# JMP_1_1.net
KiCad netlist of a schematic drawn in EAGLE
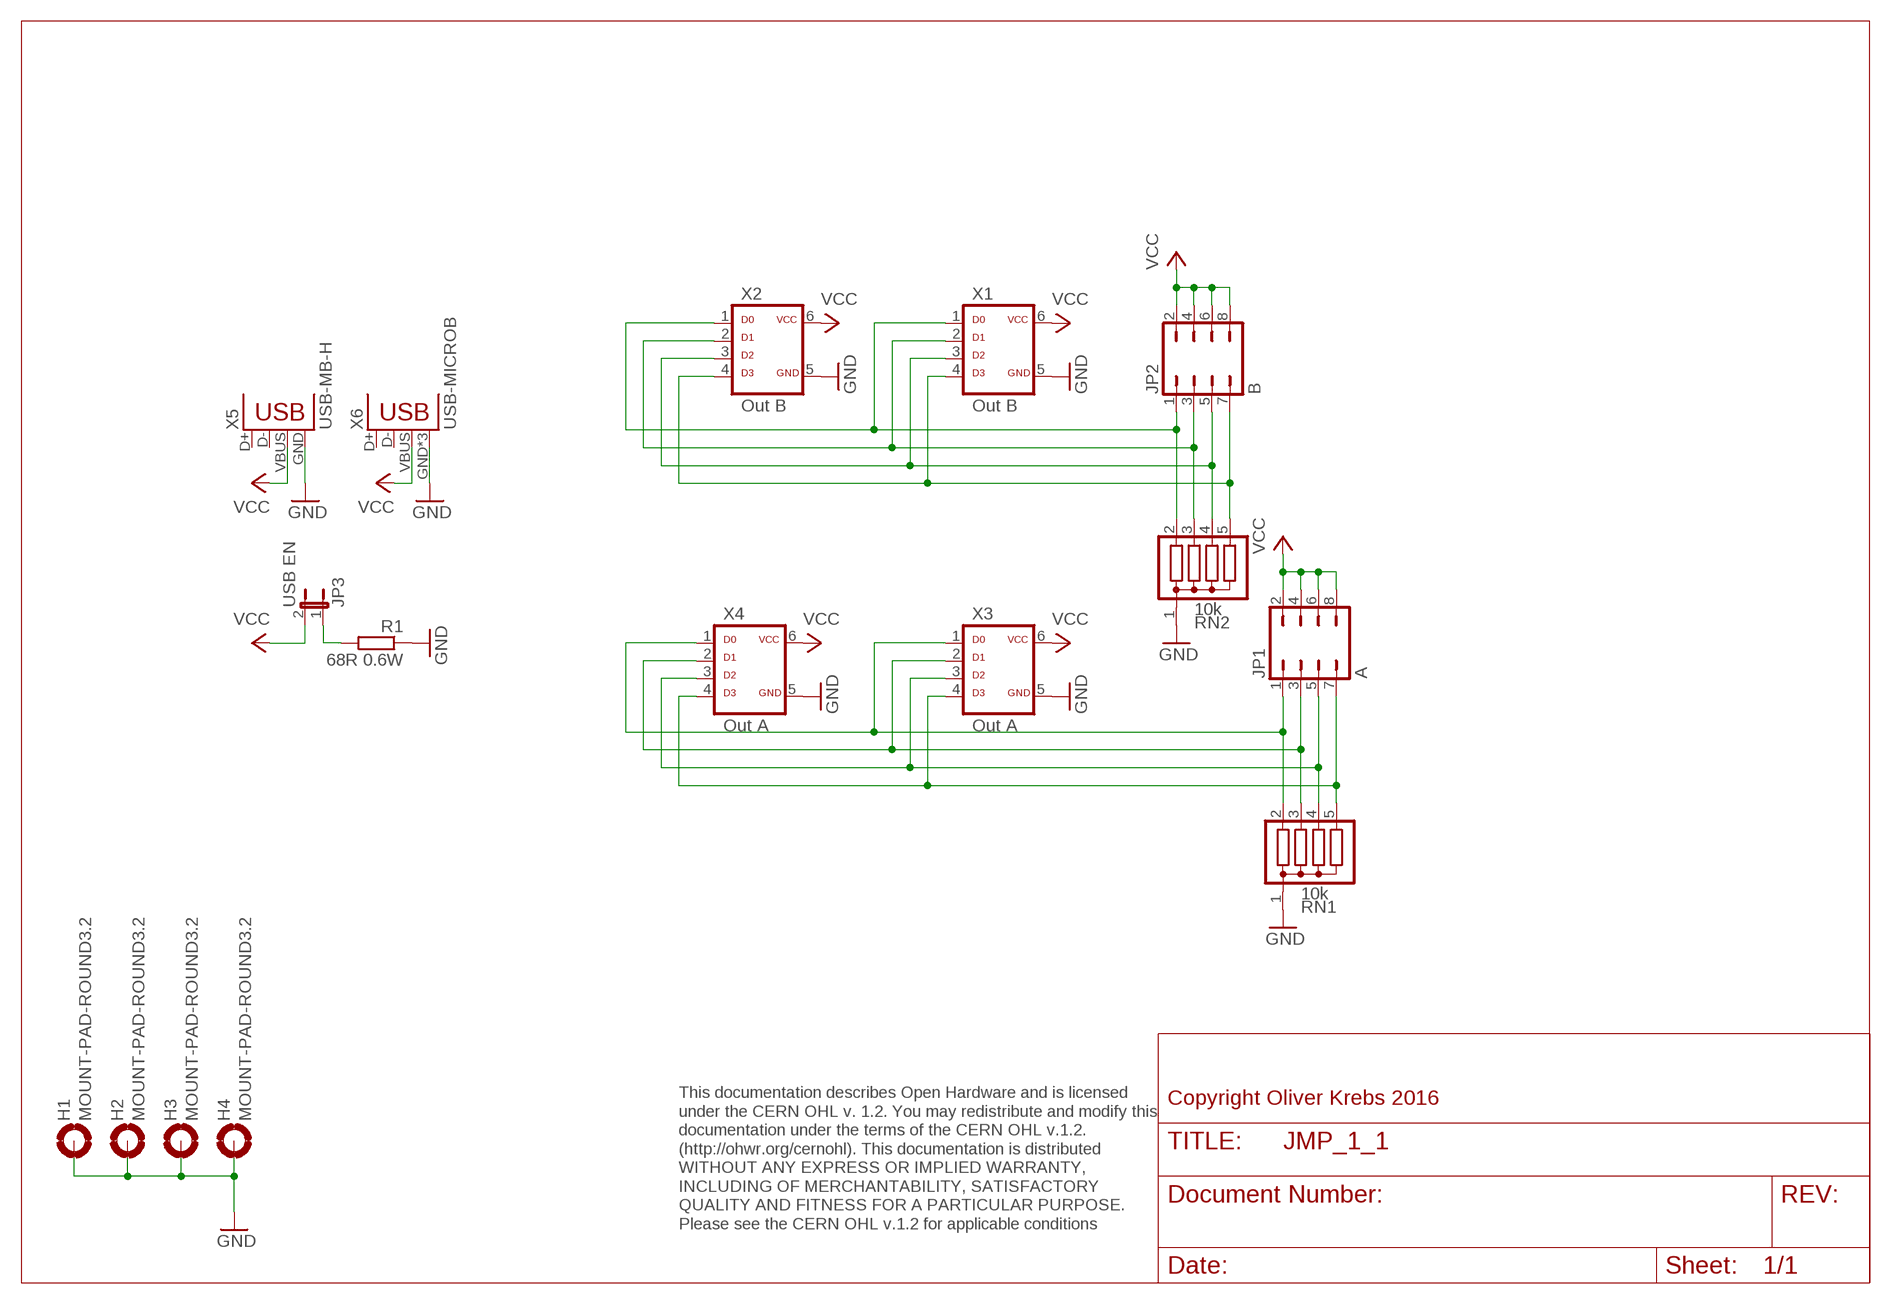
[diagram p0: schematic, sheet 1]

(export (version "E")
  (design (tool "Eeschema 10.0.6"))
  (components
    (comp (ref "H1")
      (value "MOUNT-PAD-ROUND3.2")
      (footprint "eagle-import:3,2-PAD")
      (libsource (lib "eagle-import") (part "MOUNT-PAD-ROUND3.2"))
    )
    (comp (ref "H2")
      (value "MOUNT-PAD-ROUND3.2")
      (footprint "eagle-import:3,2-PAD")
      (libsource (lib "eagle-import") (part "MOUNT-PAD-ROUND3.2"))
    )
    (comp (ref "H3")
      (value "MOUNT-PAD-ROUND3.2")
      (footprint "eagle-import:3,2-PAD")
      (libsource (lib "eagle-import") (part "MOUNT-PAD-ROUND3.2"))
    )
    (comp (ref "H4")
      (value "MOUNT-PAD-ROUND3.2")
      (footprint "eagle-import:3,2-PAD")
      (libsource (lib "eagle-import") (part "MOUNT-PAD-ROUND3.2"))
    )
    (comp (ref "JP1")
      (value "A")
      (footprint "eagle-import:JP4Q")
      (libsource (lib "eagle-import") (part "JP4Q"))
    )
    (comp (ref "JP2")
      (value "B")
      (footprint "eagle-import:JP4Q")
      (libsource (lib "eagle-import") (part "JP4Q"))
    )
    (comp (ref "JP3")
      (value "USB EN")
      (footprint "eagle-import:JP1")
      (libsource (lib "eagle-import") (part "JP1E"))
    )
    (comp (ref "R1")
      (value "68R 0.6W")
      (footprint "eagle-import:0207_10")
      (libsource (lib "eagle-import") (part "R-EU_0207/10"))
    )
    (comp (ref "RN1")
      (value "10k")
      (footprint "eagle-import:SIL5")
      (libsource (lib "eagle-import") (part "G04R"))
    )
    (comp (ref "RN2")
      (value "10k")
      (footprint "eagle-import:SIL5")
      (libsource (lib "eagle-import") (part "G04R"))
    )
    (comp (ref "X1")
      (value "Out B")
      (footprint "eagle-import:ML-6")
      (libsource (lib "eagle-import") (part "ML6D"))
    )
    (comp (ref "X2")
      (value "Out B")
      (footprint "eagle-import:ML-6")
      (libsource (lib "eagle-import") (part "ML6D"))
    )
    (comp (ref "X3")
      (value "Out A")
      (footprint "eagle-import:ML-6")
      (libsource (lib "eagle-import") (part "ML6D"))
    )
    (comp (ref "X4")
      (value "Out A")
      (footprint "eagle-import:ML-6")
      (libsource (lib "eagle-import") (part "ML6D"))
    )
    (comp (ref "X5")
      (value "USB-MB-H")
      (footprint "eagle-import:USB-MB-H")
      (libsource (lib "eagle-import") (part "USB-MB-H"))
    )
    (comp (ref "X6")
      (value "USB-MICROB")
      (footprint "eagle-import:USB-MICROB")
      (libsource (lib "eagle-import") (part "USB-MICROB"))
    )
  )
  (nets
    (net (code "1") (name "GND") (class "Default")
      (node (ref "H1") (pin "B3,2") (pinfunction "MOUNT_B3,2") (pintype "passive"))
      (node (ref "H2") (pin "B3,2") (pinfunction "MOUNT_B3,2") (pintype "passive"))
      (node (ref "H3") (pin "B3,2") (pinfunction "MOUNT_B3,2") (pintype "passive"))
      (node (ref "H4") (pin "B3,2") (pinfunction "MOUNT_B3,2") (pintype "passive"))
      (node (ref "R1") (pin "1") (pinfunction "1_1") (pintype "passive"))
      (node (ref "RN1") (pin "1") (pinfunction "1_1") (pintype "passive"))
      (node (ref "RN2") (pin "1") (pinfunction "1_1") (pintype "passive"))
      (node (ref "X1") (pin "5") (pinfunction "5_5") (pintype "passive"))
      (node (ref "X2") (pin "5") (pinfunction "5_5") (pintype "passive"))
      (node (ref "X3") (pin "5") (pinfunction "5_5") (pintype "passive"))
      (node (ref "X4") (pin "5") (pinfunction "5_5") (pintype "passive"))
      (node (ref "X5") (pin "GND") (pinfunction "GND_GND") (pintype "bidirectional"))
      (node (ref "X6") (pin "GND") (pinfunction "GND_GND") (pintype "bidirectional"))
      (node (ref "X6") (pin "MT1") (pinfunction "GND_MT1") (pintype "bidirectional"))
      (node (ref "X6") (pin "MT2") (pinfunction "GND_MT2") (pintype "bidirectional"))
    )
    (net (code "2") (name "Net-(JP1-Pad1)") (class "Default")
      (node (ref "JP1") (pin "1") (pinfunction "1_1") (pintype "passive"))
      (node (ref "RN1") (pin "2") (pinfunction "2_2") (pintype "passive"))
      (node (ref "X3") (pin "1") (pinfunction "1_1") (pintype "passive"))
      (node (ref "X4") (pin "1") (pinfunction "1_1") (pintype "passive"))
    )
    (net (code "3") (name "Net-(JP1-Pad3)") (class "Default")
      (node (ref "JP1") (pin "3") (pinfunction "3_3") (pintype "passive"))
      (node (ref "RN1") (pin "3") (pinfunction "3_3") (pintype "passive"))
      (node (ref "X3") (pin "2") (pinfunction "2_2") (pintype "passive"))
      (node (ref "X4") (pin "2") (pinfunction "2_2") (pintype "passive"))
    )
    (net (code "4") (name "Net-(JP1-Pad5)") (class "Default")
      (node (ref "JP1") (pin "5") (pinfunction "5_5") (pintype "passive"))
      (node (ref "RN1") (pin "4") (pinfunction "4_4") (pintype "passive"))
      (node (ref "X3") (pin "3") (pinfunction "3_3") (pintype "passive"))
      (node (ref "X4") (pin "3") (pinfunction "3_3") (pintype "passive"))
    )
    (net (code "5") (name "Net-(JP1-Pad7)") (class "Default")
      (node (ref "JP1") (pin "7") (pinfunction "7_7") (pintype "passive"))
      (node (ref "RN1") (pin "5") (pinfunction "5_5") (pintype "passive"))
      (node (ref "X3") (pin "4") (pinfunction "4_4") (pintype "passive"))
      (node (ref "X4") (pin "4") (pinfunction "4_4") (pintype "passive"))
    )
    (net (code "6") (name "Net-(JP2-Pad1)") (class "Default")
      (node (ref "JP2") (pin "1") (pinfunction "1_1") (pintype "passive"))
      (node (ref "RN2") (pin "2") (pinfunction "2_2") (pintype "passive"))
      (node (ref "X1") (pin "1") (pinfunction "1_1") (pintype "passive"))
      (node (ref "X2") (pin "1") (pinfunction "1_1") (pintype "passive"))
    )
    (net (code "7") (name "Net-(JP2-Pad3)") (class "Default")
      (node (ref "JP2") (pin "3") (pinfunction "3_3") (pintype "passive"))
      (node (ref "RN2") (pin "3") (pinfunction "3_3") (pintype "passive"))
      (node (ref "X1") (pin "2") (pinfunction "2_2") (pintype "passive"))
      (node (ref "X2") (pin "2") (pinfunction "2_2") (pintype "passive"))
    )
    (net (code "8") (name "Net-(JP2-Pad5)") (class "Default")
      (node (ref "JP2") (pin "5") (pinfunction "5_5") (pintype "passive"))
      (node (ref "RN2") (pin "4") (pinfunction "4_4") (pintype "passive"))
      (node (ref "X1") (pin "3") (pinfunction "3_3") (pintype "passive"))
      (node (ref "X2") (pin "3") (pinfunction "3_3") (pintype "passive"))
    )
    (net (code "9") (name "Net-(JP2-Pad7)") (class "Default")
      (node (ref "JP2") (pin "7") (pinfunction "7_7") (pintype "passive"))
      (node (ref "RN2") (pin "5") (pinfunction "5_5") (pintype "passive"))
      (node (ref "X1") (pin "4") (pinfunction "4_4") (pintype "passive"))
      (node (ref "X2") (pin "4") (pinfunction "4_4") (pintype "passive"))
    )
    (net (code "10") (name "Net-(JP3-Pad1)") (class "Default")
      (node (ref "JP3") (pin "1") (pinfunction "1_1") (pintype "passive"))
      (node (ref "R1") (pin "2") (pinfunction "2_2") (pintype "passive"))
    )
    (net (code "11") (name "VCC") (class "Default")
      (node (ref "JP1") (pin "2") (pinfunction "2_2") (pintype "passive"))
      (node (ref "JP1") (pin "4") (pinfunction "4_4") (pintype "passive"))
      (node (ref "JP1") (pin "6") (pinfunction "6_6") (pintype "passive"))
      (node (ref "JP1") (pin "8") (pinfunction "8_8") (pintype "passive"))
      (node (ref "JP2") (pin "2") (pinfunction "2_2") (pintype "passive"))
      (node (ref "JP2") (pin "4") (pinfunction "4_4") (pintype "passive"))
      (node (ref "JP2") (pin "6") (pinfunction "6_6") (pintype "passive"))
      (node (ref "JP2") (pin "8") (pinfunction "8_8") (pintype "passive"))
      (node (ref "JP3") (pin "2") (pinfunction "2_2") (pintype "passive"))
      (node (ref "X1") (pin "6") (pinfunction "6_6") (pintype "passive"))
      (node (ref "X2") (pin "6") (pinfunction "6_6") (pintype "passive"))
      (node (ref "X3") (pin "6") (pinfunction "6_6") (pintype "passive"))
      (node (ref "X4") (pin "6") (pinfunction "6_6") (pintype "passive"))
      (node (ref "X5") (pin "VBUS") (pinfunction "VBUS_VBUS") (pintype "bidirectional"))
      (node (ref "X6") (pin "VBUS") (pinfunction "VBUS_VBUS") (pintype "bidirectional"))
    )
    (net (code "12") (name "unconnected-(X5-PadD+)") (class "Default")
      (node (ref "X5") (pin "D+") (pinfunction "D+_D+") (pintype "bidirectional"))
    )
    (net (code "13") (name "unconnected-(X5-PadD-)") (class "Default")
      (node (ref "X5") (pin "D-") (pinfunction "D-_D-") (pintype "bidirectional"))
    )
    (net (code "14") (name "unconnected-(X6-PadD+)") (class "Default")
      (node (ref "X6") (pin "D+") (pinfunction "D+_D+") (pintype "bidirectional"))
    )
    (net (code "15") (name "unconnected-(X6-PadD-)") (class "Default")
      (node (ref "X6") (pin "D-") (pinfunction "D-_D-") (pintype "bidirectional"))
    )
  )
)
